# Current-to-Voltage-Sc.net
KiCad netlist of a schematic drawn in Altium Designer
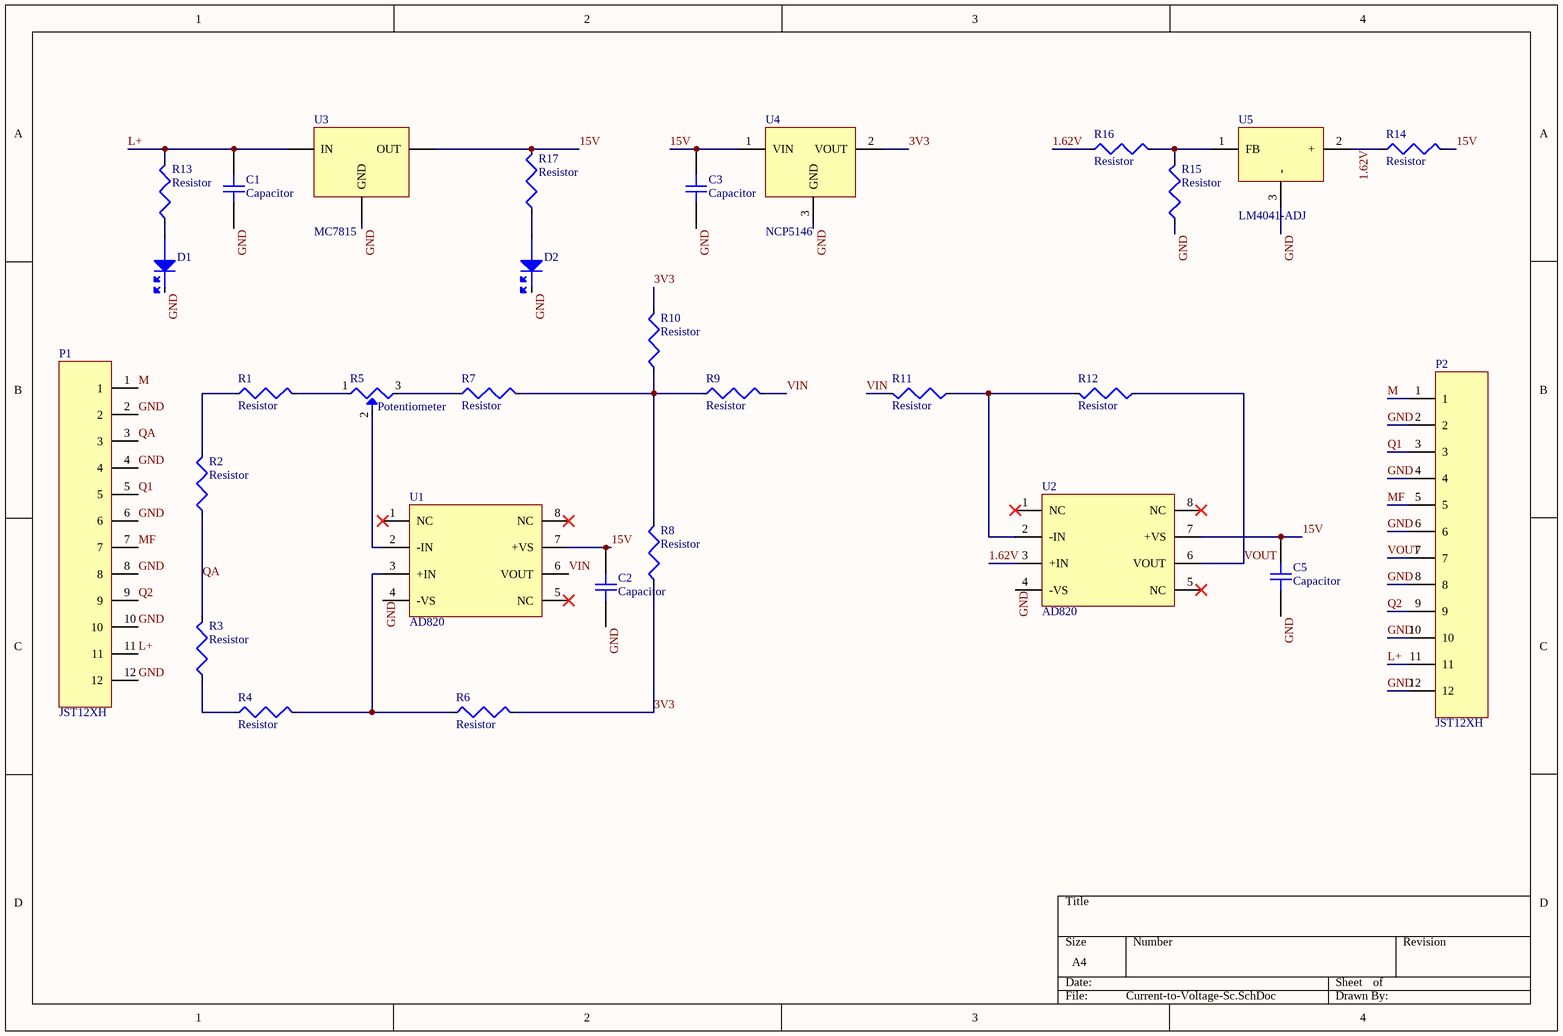
[diagram p0: Current-to-Voltage-Sc.SchDoc]

(export (version "E")
  (design (tool "Eeschema 10.0.6"))
  (components
    (comp (ref "C1")
      (value "Capacitor")
      (footprint "C0805")
      (libsource (lib "Current-to-Voltage-Schlib") (part "Capacitor"))
    )
    (comp (ref "C2")
      (value "Capacitor")
      (footprint "C0805")
      (libsource (lib "Current-to-Voltage-Schlib") (part "Capacitor"))
    )
    (comp (ref "C3")
      (value "Capacitor")
      (footprint "C0805")
      (libsource (lib "Current-to-Voltage-Schlib") (part "Capacitor"))
    )
    (comp (ref "C5")
      (value "Capacitor")
      (footprint "C0805")
      (libsource (lib "Current-to-Voltage-Schlib") (part "Capacitor"))
    )
    (comp (ref "D1")
      (value "LED")
      (footprint "LED0805")
      (libsource (lib "Current-to-Voltage-Schlib") (part "LED"))
    )
    (comp (ref "D2")
      (value "LED")
      (footprint "LED0805")
      (libsource (lib "Current-to-Voltage-Schlib") (part "LED"))
    )
    (comp (ref "P1") (value "JST12XH") (footprint "JST12XH") (libsource (lib "") (part "JST12XH_1")))
    (comp (ref "P2")
      (value "JST12XH")
      (footprint "JST12XH")
      (libsource (lib "Current-to-Voltage-Schlib") (part "JST12XH"))
    )
    (comp (ref "R1")
      (value "Resistor")
      (footprint "R0805 - duplicate2")
      (libsource (lib "Current-to-Voltage-Schlib") (part "Resistor"))
    )
    (comp (ref "R2")
      (value "Resistor")
      (footprint "R0805 - duplicate2")
      (libsource (lib "Current-to-Voltage-Schlib") (part "Resistor"))
    )
    (comp (ref "R3")
      (value "Resistor")
      (footprint "R0805 - duplicate2")
      (libsource (lib "Current-to-Voltage-Schlib") (part "Resistor"))
    )
    (comp (ref "R4")
      (value "Resistor")
      (footprint "R0805 - duplicate2")
      (libsource (lib "Current-to-Voltage-Schlib") (part "Resistor"))
    )
    (comp (ref "R5")
      (value "Potentiometer")
      (footprint "POT3")
      (libsource (lib "Current-to-Voltage-Schlib") (part "Potentiometer"))
    )
    (comp (ref "R6")
      (value "Resistor")
      (footprint "R0805 - duplicate2")
      (libsource (lib "Current-to-Voltage-Schlib") (part "Resistor"))
    )
    (comp (ref "R7")
      (value "Resistor")
      (footprint "R0805 - duplicate2")
      (libsource (lib "Current-to-Voltage-Schlib") (part "Resistor"))
    )
    (comp (ref "R8")
      (value "Resistor")
      (footprint "R0805 - duplicate2")
      (libsource (lib "Current-to-Voltage-Schlib") (part "Resistor"))
    )
    (comp (ref "R9")
      (value "Resistor")
      (footprint "R0805 - duplicate2")
      (libsource (lib "Current-to-Voltage-Schlib") (part "Resistor"))
    )
    (comp (ref "R10")
      (value "Resistor")
      (footprint "R0805 - duplicate2")
      (libsource (lib "Current-to-Voltage-Schlib") (part "Resistor"))
    )
    (comp (ref "R11")
      (value "Resistor")
      (footprint "R0805 - duplicate2")
      (libsource (lib "Current-to-Voltage-Schlib") (part "Resistor"))
    )
    (comp (ref "R12")
      (value "Resistor")
      (footprint "R0805 - duplicate2")
      (libsource (lib "Current-to-Voltage-Schlib") (part "Resistor"))
    )
    (comp (ref "R13")
      (value "Resistor")
      (footprint "R0805 - duplicate2")
      (libsource (lib "Current-to-Voltage-Schlib") (part "Resistor"))
    )
    (comp (ref "R14")
      (value "Resistor")
      (footprint "R0805 - duplicate2")
      (libsource (lib "Current-to-Voltage-Schlib") (part "Resistor"))
    )
    (comp (ref "R15")
      (value "Resistor")
      (footprint "R1206 - duplicate")
      (libsource (lib "Current-to-Voltage-Schlib") (part "Resistor"))
    )
    (comp (ref "R16")
      (value "Resistor")
      (footprint "R0805 - duplicate2")
      (libsource (lib "Current-to-Voltage-Schlib") (part "Resistor"))
    )
    (comp (ref "R17")
      (value "Resistor")
      (footprint "R0805 - duplicate2")
      (libsource (lib "Current-to-Voltage-Schlib") (part "Resistor"))
    )
    (comp (ref "U1")
      (value "AD820")
      (footprint "SOIC127P600X175-8N")
      (libsource (lib "Current-to-Voltage-Schlib") (part "AD820"))
    )
    (comp (ref "U2")
      (value "AD820")
      (footprint "SOIC127P600X175-8N")
      (libsource (lib "Current-to-Voltage-Schlib") (part "AD820"))
    )
    (comp (ref "U3")
      (value "MC7815")
      (footprint "DPAK229P991X238-3N")
      (libsource (lib "Current-to-Voltage-Schlib") (part "MC7815"))
    )
    (comp (ref "U4")
      (value "NCP5146")
      (footprint "SOT95P237X110-3N")
      (libsource (lib "Current-to-Voltage-Schlib") (part "NCP5146"))
    )
    (comp (ref "U5")
      (value "LM4041-ADJ")
      (footprint "SOT95P237X110-3N")
      (libsource (lib "Current-to-Voltage-Schlib") (part "LM4041-ADJ"))
    )
  )
  (nets
    (net (code "1") (name "/1.62V") (class "Default")
      (node (ref "R14") (pin "1") (pinfunction "1_1") (pintype "passive"))
      (node (ref "R16") (pin "1") (pinfunction "1_1") (pintype "passive"))
      (node (ref "U2") (pin "3") (pinfunction "+IN_3") (pintype "passive"))
      (node (ref "U5") (pin "2") (pinfunction "+_2") (pintype "passive"))
    )
    (net (code "2") (name "/3V3") (class "Default")
      (node (ref "R10") (pin "2") (pinfunction "2_2") (pintype "passive"))
      (node (ref "R6") (pin "2") (pinfunction "2_2") (pintype "passive"))
      (node (ref "R8") (pin "1") (pinfunction "1_1") (pintype "passive"))
      (node (ref "U4") (pin "2") (pinfunction "VOUT_2") (pintype "passive"))
    )
    (net (code "3") (name "/15V") (class "Default")
      (node (ref "C2") (pin "2") (pinfunction "2_2") (pintype "passive"))
      (node (ref "C3") (pin "2") (pinfunction "2_2") (pintype "passive"))
      (node (ref "C5") (pin "2") (pinfunction "2_2") (pintype "passive"))
      (node (ref "R14") (pin "2") (pinfunction "2_2") (pintype "passive"))
      (node (ref "R17") (pin "2") (pinfunction "2_2") (pintype "passive"))
      (node (ref "U1") (pin "7") (pinfunction "+VS_7") (pintype "passive"))
      (node (ref "U2") (pin "7") (pinfunction "+VS_7") (pintype "passive"))
      (node (ref "U3") (pin "3") (pinfunction "OUT_3") (pintype "passive"))
      (node (ref "U4") (pin "1") (pinfunction "VIN_1") (pintype "passive"))
    )
    (net (code "4") (name "/GND") (class "Default")
      (node (ref "C1") (pin "1") (pinfunction "1_1") (pintype "passive"))
      (node (ref "C2") (pin "1") (pinfunction "1_1") (pintype "passive"))
      (node (ref "C3") (pin "1") (pinfunction "1_1") (pintype "passive"))
      (node (ref "C5") (pin "1") (pinfunction "1_1") (pintype "passive"))
      (node (ref "D1") (pin "1") (pinfunction "1_1") (pintype "passive"))
      (node (ref "D2") (pin "1") (pinfunction "1_1") (pintype "passive"))
      (node (ref "P1") (pin "10") (pinfunction "10_10") (pintype "passive"))
      (node (ref "P1") (pin "12") (pinfunction "12_12") (pintype "passive"))
      (node (ref "P1") (pin "2") (pinfunction "2_2") (pintype "passive"))
      (node (ref "P1") (pin "4") (pinfunction "4_4") (pintype "passive"))
      (node (ref "P1") (pin "6") (pinfunction "6_6") (pintype "passive"))
      (node (ref "P1") (pin "8") (pinfunction "8_8") (pintype "passive"))
      (node (ref "P2") (pin "10") (pinfunction "10_10") (pintype "passive"))
      (node (ref "P2") (pin "12") (pinfunction "12_12") (pintype "passive"))
      (node (ref "P2") (pin "2") (pinfunction "2_2") (pintype "passive"))
      (node (ref "P2") (pin "4") (pinfunction "4_4") (pintype "passive"))
      (node (ref "P2") (pin "6") (pinfunction "6_6") (pintype "passive"))
      (node (ref "P2") (pin "8") (pinfunction "8_8") (pintype "passive"))
      (node (ref "R15") (pin "1") (pinfunction "1_1") (pintype "passive"))
      (node (ref "U1") (pin "4") (pinfunction "-VS_4") (pintype "passive"))
      (node (ref "U2") (pin "4") (pinfunction "-VS_4") (pintype "passive"))
      (node (ref "U3") (pin "2") (pinfunction "GND_2") (pintype "passive"))
      (node (ref "U4") (pin "3") (pinfunction "GND_3") (pintype "passive"))
      (node (ref "U5") (pin "3") (pinfunction "-_3") (pintype "passive"))
    )
    (net (code "5") (name "/L+") (class "Default")
      (node (ref "C1") (pin "2") (pinfunction "2_2") (pintype "passive"))
      (node (ref "P1") (pin "11") (pinfunction "11_11") (pintype "passive"))
      (node (ref "P2") (pin "11") (pinfunction "11_11") (pintype "passive"))
      (node (ref "R13") (pin "2") (pinfunction "2_2") (pintype "passive"))
      (node (ref "U3") (pin "1") (pinfunction "IN_1") (pintype "passive"))
    )
    (net (code "6") (name "/M") (class "Default")
      (node (ref "P1") (pin "1") (pinfunction "1_1") (pintype "passive"))
      (node (ref "P2") (pin "1") (pinfunction "1_1") (pintype "passive"))
    )
    (net (code "7") (name "/MF") (class "Default")
      (node (ref "P1") (pin "7") (pinfunction "7_7") (pintype "passive"))
      (node (ref "P2") (pin "5") (pinfunction "5_5") (pintype "passive"))
    )
    (net (code "8") (name "/Q1") (class "Default")
      (node (ref "P1") (pin "5") (pinfunction "5_5") (pintype "passive"))
      (node (ref "P2") (pin "3") (pinfunction "3_3") (pintype "passive"))
    )
    (net (code "9") (name "/Q2") (class "Default")
      (node (ref "P1") (pin "9") (pinfunction "9_9") (pintype "passive"))
      (node (ref "P2") (pin "9") (pinfunction "9_9") (pintype "passive"))
    )
    (net (code "10") (name "/QA") (class "Default")
      (node (ref "P1") (pin "3") (pinfunction "3_3") (pintype "passive"))
      (node (ref "R2") (pin "1") (pinfunction "1_1") (pintype "passive"))
      (node (ref "R3") (pin "2") (pinfunction "2_2") (pintype "passive"))
    )
    (net (code "11") (name "/VIN") (class "Default")
      (node (ref "R11") (pin "2") (pinfunction "2_2") (pintype "passive"))
      (node (ref "R9") (pin "2") (pinfunction "2_2") (pintype "passive"))
      (node (ref "U1") (pin "6") (pinfunction "VOUT_6") (pintype "passive"))
    )
    (net (code "12") (name "/VOUT") (class "Default")
      (node (ref "P2") (pin "7") (pinfunction "7_7") (pintype "passive"))
      (node (ref "R12") (pin "1") (pinfunction "1_1") (pintype "passive"))
      (node (ref "U2") (pin "6") (pinfunction "VOUT_6") (pintype "passive"))
    )
    (net (code "13") (name "Net-(D1-Pad2)") (class "Default")
      (node (ref "D1") (pin "2") (pinfunction "2_2") (pintype "passive"))
      (node (ref "R13") (pin "1") (pinfunction "1_1") (pintype "passive"))
    )
    (net (code "14") (name "Net-(D2-Pad2)") (class "Default")
      (node (ref "D2") (pin "2") (pinfunction "2_2") (pintype "passive"))
      (node (ref "R17") (pin "1") (pinfunction "1_1") (pintype "passive"))
    )
    (net (code "15") (name "Net-(R1-Pad1)") (class "Default")
      (node (ref "R1") (pin "1") (pinfunction "1_1") (pintype "passive"))
      (node (ref "R2") (pin "2") (pinfunction "2_2") (pintype "passive"))
    )
    (net (code "16") (name "Net-(R1-Pad2)") (class "Default")
      (node (ref "R1") (pin "2") (pinfunction "2_2") (pintype "passive"))
      (node (ref "R5") (pin "1") (pinfunction "1_1") (pintype "passive"))
    )
    (net (code "17") (name "Net-(R3-Pad1)") (class "Default")
      (node (ref "R3") (pin "1") (pinfunction "1_1") (pintype "passive"))
      (node (ref "R4") (pin "1") (pinfunction "1_1") (pintype "passive"))
    )
    (net (code "18") (name "Net-(R5-Pad3)") (class "Default")
      (node (ref "R5") (pin "3") (pinfunction "3_3") (pintype "passive"))
      (node (ref "R7") (pin "1") (pinfunction "1_1") (pintype "passive"))
    )
    (net (code "19") (name "Net-(R10-Pad1)") (class "Default")
      (node (ref "R10") (pin "1") (pinfunction "1_1") (pintype "passive"))
      (node (ref "R7") (pin "2") (pinfunction "2_2") (pintype "passive"))
      (node (ref "R8") (pin "2") (pinfunction "2_2") (pintype "passive"))
      (node (ref "R9") (pin "1") (pinfunction "1_1") (pintype "passive"))
    )
    (net (code "20") (name "Net-(U1-+IN)") (class "Default")
      (node (ref "R4") (pin "2") (pinfunction "2_2") (pintype "passive"))
      (node (ref "R6") (pin "1") (pinfunction "1_1") (pintype "passive"))
      (node (ref "U1") (pin "3") (pinfunction "+IN_3") (pintype "passive"))
    )
    (net (code "21") (name "Net-(U1--IN)") (class "Default")
      (node (ref "R5") (pin "2") (pinfunction "2_2") (pintype "passive"))
      (node (ref "U1") (pin "2") (pinfunction "-IN_2") (pintype "passive"))
    )
    (net (code "22") (name "Net-(U2--IN)") (class "Default")
      (node (ref "R11") (pin "1") (pinfunction "1_1") (pintype "passive"))
      (node (ref "R12") (pin "2") (pinfunction "2_2") (pintype "passive"))
      (node (ref "U2") (pin "2") (pinfunction "-IN_2") (pintype "passive"))
    )
    (net (code "23") (name "Net-(U5-FB)") (class "Default")
      (node (ref "R15") (pin "2") (pinfunction "2_2") (pintype "passive"))
      (node (ref "R16") (pin "2") (pinfunction "2_2") (pintype "passive"))
      (node (ref "U5") (pin "1") (pinfunction "FB_1") (pintype "passive"))
    )
    (net (code "24") (name "unconnected-(U1-NC-Pad1)") (class "Default")
      (node (ref "U1") (pin "1") (pinfunction "NC_1") (pintype "passive+no_connect"))
    )
    (net (code "25") (name "unconnected-(U1-NC-Pad5)") (class "Default")
      (node (ref "U1") (pin "5") (pinfunction "NC_5") (pintype "passive+no_connect"))
    )
    (net (code "26") (name "unconnected-(U1-NC-Pad8)") (class "Default")
      (node (ref "U1") (pin "8") (pinfunction "NC_8") (pintype "passive+no_connect"))
    )
    (net (code "27") (name "unconnected-(U2-NC-Pad1)") (class "Default")
      (node (ref "U2") (pin "1") (pinfunction "NC_1") (pintype "passive+no_connect"))
    )
    (net (code "28") (name "unconnected-(U2-NC-Pad5)") (class "Default")
      (node (ref "U2") (pin "5") (pinfunction "NC_5") (pintype "passive+no_connect"))
    )
    (net (code "29") (name "unconnected-(U2-NC-Pad8)") (class "Default")
      (node (ref "U2") (pin "8") (pinfunction "NC_8") (pintype "passive+no_connect"))
    )
  )
)
